# TailBoard.net
KiCad netlist of a schematic drawn in Altium Designer
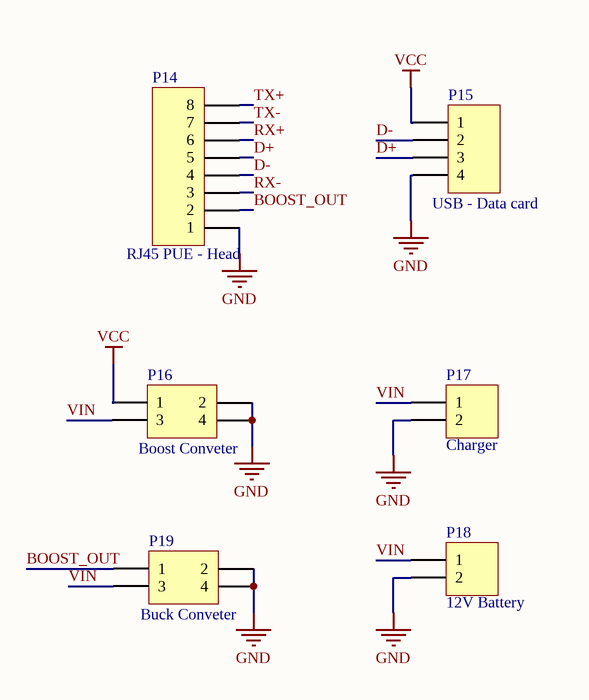
[diagram p0: TailBoard.SchDoc]

(export (version "E")
  (design (tool "Eeschema 10.0.6"))
  (components
    (comp (ref "P14")
      (value "RJ45 PUE - Head")
      (footprint "RJ45")
      (description "Header, 8-Pin")
      (fields (field (name "PUBLISHER") "Altium Limited"))
      (libsource (lib "Miscellaneous Connectors") (part "Header 8"))
    )
    (comp (ref "P15")
      (value "USB - Data card")
      (footprint "USB_Female")
      (description "Header, 4-Pin")
      (fields (field (name "PUBLISHER") "Altium Limited"))
      (libsource (lib "Miscellaneous Connectors") (part "Header 4"))
    )
    (comp (ref "P16")
      (value "Boost Conveter")
      (footprint "HDR2X2")
      (description "Header, 2-Pin, Dual row")
      (fields (field (name "PUBLISHER") "Altium Limited"))
      (libsource (lib "Miscellaneous Connectors") (part "Header 2X2"))
    )
    (comp (ref "P17")
      (value "Charger")
      (footprint "HDR1X2")
      (description "Header, 2-Pin")
      (fields (field (name "PUBLISHER") "Altium Limited"))
      (libsource (lib "Miscellaneous Connectors") (part "Header 2"))
    )
    (comp (ref "P18")
      (value "12V Battery")
      (footprint "HDR1X2")
      (description "Header, 2-Pin")
      (fields (field (name "PUBLISHER") "Altium Limited"))
      (libsource (lib "Miscellaneous Connectors") (part "Header 2"))
    )
    (comp (ref "P19")
      (value "Buck Conveter")
      (footprint "HDR2X2")
      (description "Header, 2-Pin, Dual row")
      (fields (field (name "PUBLISHER") "Altium Limited"))
      (libsource (lib "Miscellaneous Connectors") (part "Header 2X2"))
    )
  )
  (nets
    (net (code "1") (name "/BOOST_OUT") (class "Default")
      (node (ref "P14") (pin "2") (pinfunction "2_2") (pintype "passive"))
      (node (ref "P19") (pin "1") (pinfunction "1_1") (pintype "passive"))
    )
    (net (code "2") (name "/D+") (class "Default")
      (node (ref "P14") (pin "5") (pinfunction "5_5") (pintype "passive"))
      (node (ref "P15") (pin "3") (pinfunction "3_3") (pintype "passive"))
    )
    (net (code "3") (name "/D-") (class "Default")
      (node (ref "P14") (pin "4") (pinfunction "4_4") (pintype "passive"))
      (node (ref "P15") (pin "2") (pinfunction "2_2") (pintype "passive"))
    )
    (net (code "4") (name "/RX+") (class "Default")
      (node (ref "P14") (pin "6") (pinfunction "6_6") (pintype "passive"))
    )
    (net (code "5") (name "/RX-") (class "Default")
      (node (ref "P14") (pin "3") (pinfunction "3_3") (pintype "passive"))
    )
    (net (code "6") (name "/TX+") (class "Default")
      (node (ref "P14") (pin "8") (pinfunction "8_8") (pintype "passive"))
    )
    (net (code "7") (name "/TX-") (class "Default")
      (node (ref "P14") (pin "7") (pinfunction "7_7") (pintype "passive"))
    )
    (net (code "8") (name "/VIN") (class "Default")
      (node (ref "P16") (pin "3") (pinfunction "3_3") (pintype "passive"))
      (node (ref "P17") (pin "1") (pinfunction "1_1") (pintype "passive"))
      (node (ref "P18") (pin "1") (pinfunction "1_1") (pintype "passive"))
      (node (ref "P19") (pin "3") (pinfunction "3_3") (pintype "passive"))
    )
    (net (code "9") (name "GND") (class "Default")
      (node (ref "P14") (pin "1") (pinfunction "1_1") (pintype "passive"))
      (node (ref "P15") (pin "4") (pinfunction "4_4") (pintype "passive"))
      (node (ref "P16") (pin "2") (pinfunction "2_2") (pintype "passive"))
      (node (ref "P16") (pin "4") (pinfunction "4_4") (pintype "passive"))
      (node (ref "P17") (pin "2") (pinfunction "2_2") (pintype "passive"))
      (node (ref "P18") (pin "2") (pinfunction "2_2") (pintype "passive"))
      (node (ref "P19") (pin "2") (pinfunction "2_2") (pintype "passive"))
      (node (ref "P19") (pin "4") (pinfunction "4_4") (pintype "passive"))
    )
    (net (code "10") (name "VCC") (class "Default")
      (node (ref "P15") (pin "1") (pinfunction "1_1") (pintype "passive"))
      (node (ref "P16") (pin "1") (pinfunction "1_1") (pintype "passive"))
    )
  )
)
